# tick-box-1591b-mk-1_0.net
KiCad netlist of a schematic drawn in EAGLE
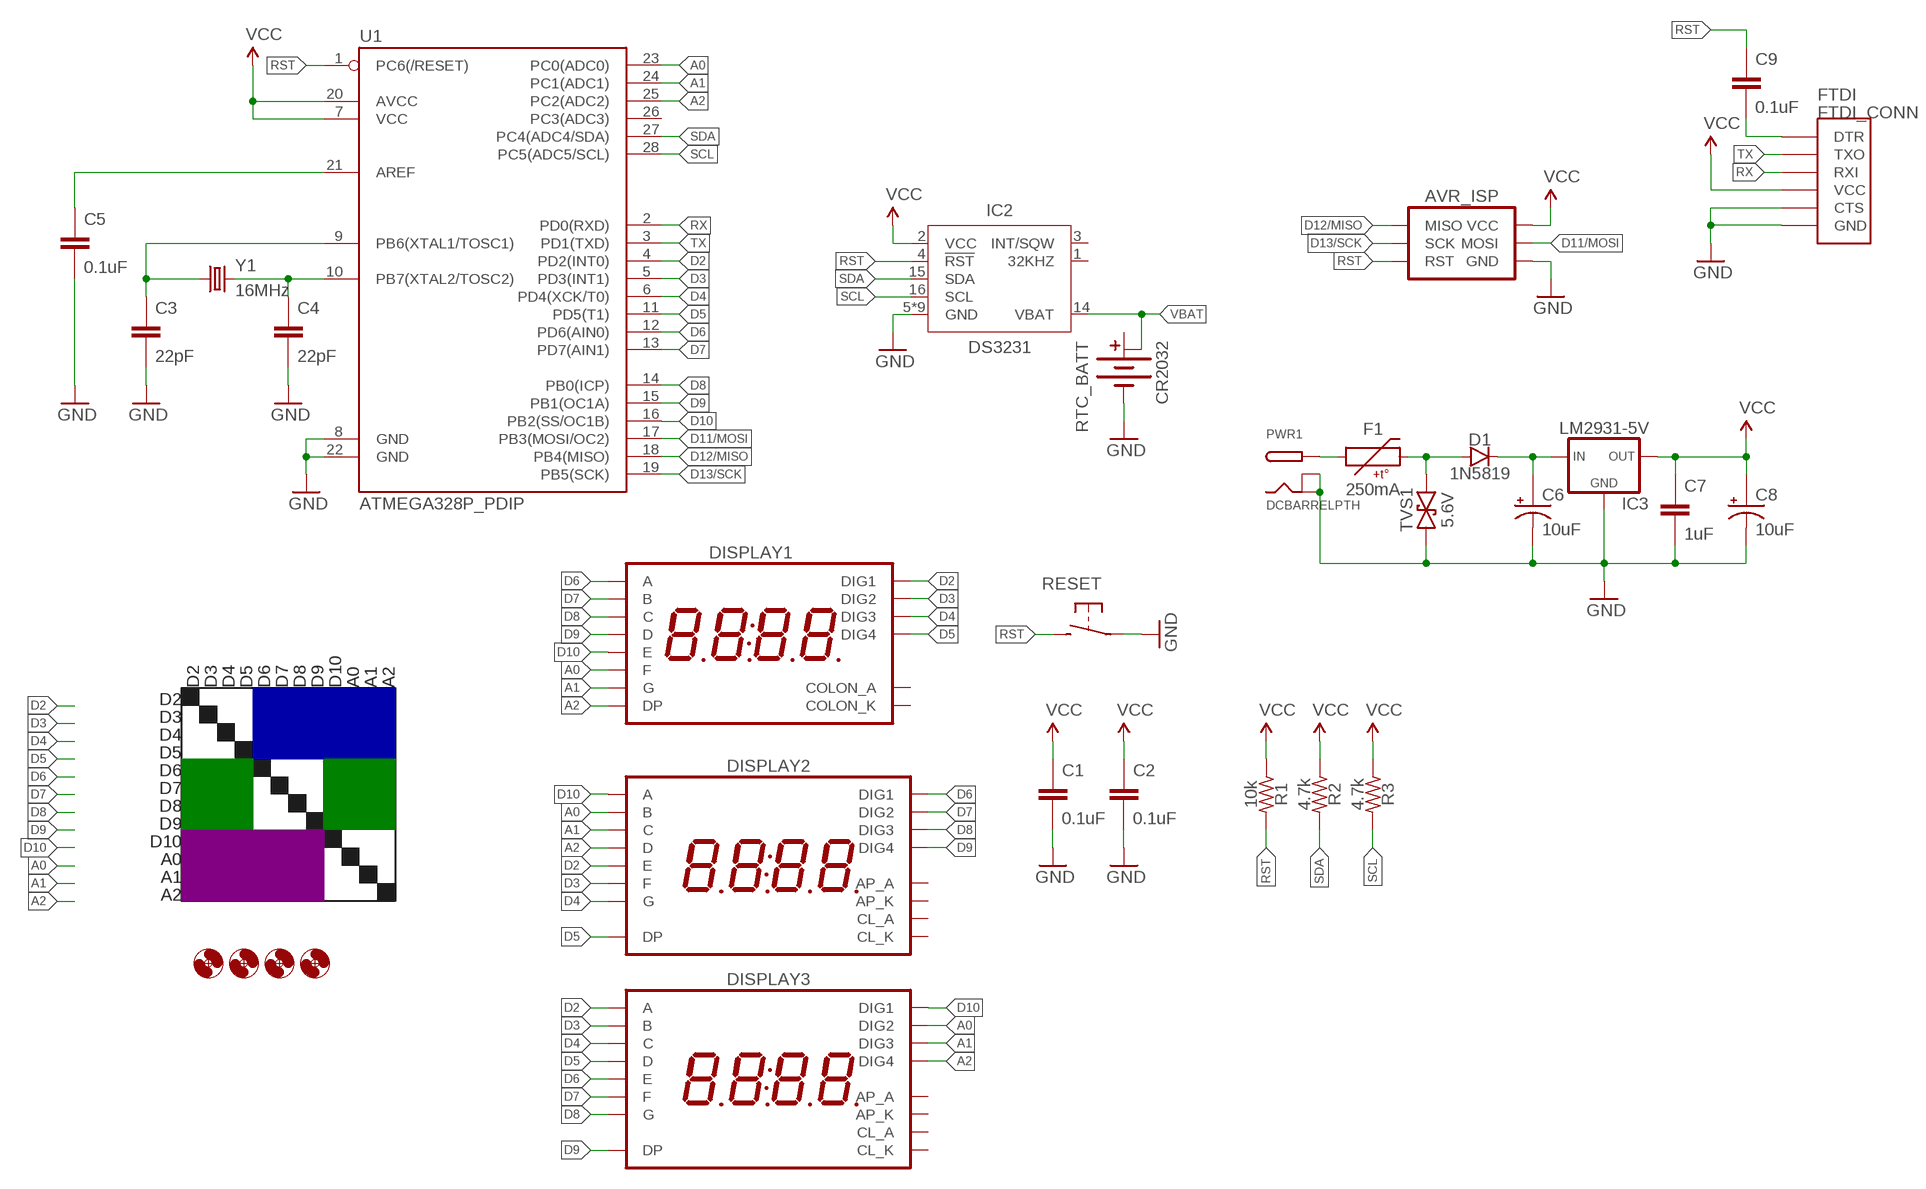
[diagram p0: schematic, sheet 1]

(export (version "E")
  (design (tool "Eeschema 10.0.6"))
  (components
    (comp (ref "AVR_ISP")
      (value "AVR_SPI_PRG_6PTH")
      (footprint "eagle-import:2X3")
      (libsource (lib "eagle-import") (part "AVR_SPI_PRG_6PTH"))
    )
    (comp (ref "C1")
      (value "0.1uF")
      (footprint "eagle-import:C025-024X044")
      (libsource (lib "eagle-import") (part "CAPACITOR-CERAMIC025-024X044"))
    )
    (comp (ref "C2")
      (value "0.1uF")
      (footprint "eagle-import:C025-024X044")
      (libsource (lib "eagle-import") (part "CAPACITOR-CERAMIC025-024X044"))
    )
    (comp (ref "C3")
      (value "22pF")
      (footprint "eagle-import:C025-024X044")
      (libsource (lib "eagle-import") (part "CAPACITOR-CERAMIC025-024X044"))
    )
    (comp (ref "C4")
      (value "22pF")
      (footprint "eagle-import:C025-024X044")
      (libsource (lib "eagle-import") (part "CAPACITOR-CERAMIC025-024X044"))
    )
    (comp (ref "C5")
      (value "0.1uF")
      (footprint "eagle-import:C025-024X044")
      (libsource (lib "eagle-import") (part "CAPACITOR-CERAMIC025-024X044"))
    )
    (comp (ref "C6")
      (value "10uF")
      (footprint "eagle-import:E2-5")
      (libsource (lib "eagle-import") (part "CAPACITOR-POLARIZEDE2-5"))
    )
    (comp (ref "C7")
      (value "1uF")
      (footprint "eagle-import:C025-024X044")
      (libsource (lib "eagle-import") (part "CAPACITOR-CERAMIC025-024X044"))
    )
    (comp (ref "C8")
      (value "10uF")
      (footprint "eagle-import:E2-5")
      (libsource (lib "eagle-import") (part "CAPACITOR-POLARIZEDE2-5"))
    )
    (comp (ref "C9")
      (value "0.1uF")
      (footprint "eagle-import:C025-024X044")
      (libsource (lib "eagle-import") (part "CAPACITOR-CERAMIC025-024X044"))
    )
    (comp (ref "D1")
      (value "1N5819")
      (footprint "eagle-import:DIODE-10.16MM")
      (libsource (lib "eagle-import") (part "DIODEPTH-10.68MM"))
    )
    (comp (ref "DISPLAY1")
      (value "7SEG_4DIGIT_COLON14.2MM-CC-NS")
      (footprint "eagle-import:7SEG_4DIG_NS")
      (libsource (lib "eagle-import") (part "7SEG_4DIGIT_COLON14.2MM-CC-NS"))
    )
    (comp (ref "DISPLAY2")
      (value "7SEG_4DIGIT_COLON_APOS")
      (footprint "eagle-import:7SEG_4DIG_10MM")
      (libsource (lib "eagle-import") (part "7SEG_4DIGIT_COLON_APOS"))
    )
    (comp (ref "DISPLAY3")
      (value "7SEG_4DIGIT_COLON_APOS")
      (footprint "eagle-import:7SEG_4DIG_10MM")
      (libsource (lib "eagle-import") (part "7SEG_4DIGIT_COLON_APOS"))
    )
    (comp (ref "F1")
      (value "250mA")
      (footprint "eagle-import:PTC-PTH-5.08MM")
      (libsource (lib "eagle-import") (part "PTCPTH-5.08MM"))
    )
    (comp (ref "FTDI")
      (value "FTDI_CONN")
      (footprint "eagle-import:FTDI_CONN")
      (libsource (lib "eagle-import") (part "FTDI_CONN"))
    )
    (comp (ref "H1")
      (value "HOLE#2")
      (footprint "eagle-import:HOLE-#2")
      (libsource (lib "eagle-import") (part "HOLE#2"))
    )
    (comp (ref "H2")
      (value "HOLE#2")
      (footprint "eagle-import:HOLE-#2")
      (libsource (lib "eagle-import") (part "HOLE#2"))
    )
    (comp (ref "H3")
      (value "HOLE#2")
      (footprint "eagle-import:HOLE-#2")
      (libsource (lib "eagle-import") (part "HOLE#2"))
    )
    (comp (ref "H4")
      (value "HOLE#2")
      (footprint "eagle-import:HOLE-#2")
      (libsource (lib "eagle-import") (part "HOLE#2"))
    )
    (comp (ref "IC2")
      (value "DS3231")
      (footprint "eagle-import:SO16W")
      (libsource (lib "eagle-import") (part "DS3231"))
    )
    (comp (ref "IC3")
      (value "LM2931-5V")
      (footprint "eagle-import:TO220-IGO-THERMPAD")
      (libsource (lib "eagle-import") (part "V_REG_78XXTO-220-THERMPAD"))
    )
    (comp (ref "PWR1")
      (value "DCBARRELPTH")
      (footprint "eagle-import:DCJACK_2MM_PTH")
      (libsource (lib "eagle-import") (part "DCBARRELPTH"))
    )
    (comp (ref "R1")
      (value "10k")
      (footprint "eagle-import:RESISTOR-AXIAL-PTH-7.62MM")
      (libsource (lib "eagle-import") (part "RESISTORPTH-AXIAL-7.62MM"))
    )
    (comp (ref "R2")
      (value "4.7k")
      (footprint "eagle-import:RESISTOR-AXIAL-PTH-7.62MM")
      (libsource (lib "eagle-import") (part "RESISTORPTH-AXIAL-7.62MM"))
    )
    (comp (ref "R3")
      (value "4.7k")
      (footprint "eagle-import:RESISTOR-AXIAL-PTH-7.62MM")
      (libsource (lib "eagle-import") (part "RESISTORPTH-AXIAL-7.62MM"))
    )
    (comp (ref "RESET")
      (value "SPST-NO-TACT6MM-PTH-SMALL-PADS")
      (footprint "eagle-import:DTS-6-SMALL-PADS")
      (libsource (lib "eagle-import") (part "SPST-NO-TACT6MM-PTH-SMALL-PADS"))
    )
    (comp (ref "RTC_BATT")
      (value "CR2032")
      (footprint "eagle-import:BATTCON_20MM_MINE")
      (libsource (lib "eagle-import") (part "BATTERY-COINCR2032_SMD"))
    )
    (comp (ref "TVS1")
      (value "5.6V")
      (footprint "eagle-import:DO-41-TVS")
      (libsource (lib "eagle-import") (part "TVSDO-41-TVS-BIDIRECTIONAL"))
    )
    (comp (ref "U1")
      (value "ATMEGA328P_PDIP")
      (footprint "eagle-import:DIL28-3")
      (libsource (lib "eagle-import") (part "ATMEGA328P_PDIP"))
    )
    (comp (ref "Y1")
      (value "16MHz")
      (footprint "eagle-import:HC49U-V")
      (libsource (lib "eagle-import") (part "CRYSTALHC49UV"))
    )
  )
  (nets
    (net (code "1") (name "A0") (class "Default")
      (node (ref "DISPLAY1") (pin "P$12") (pinfunction "F_P$12") (pintype "passive"))
      (node (ref "DISPLAY2") (pin "16") (pinfunction "B_16") (pintype "passive"))
      (node (ref "DISPLAY3") (pin "2") (pinfunction "DIG2_2") (pintype "passive"))
      (node (ref "U1") (pin "23") (pinfunction "PC0(ADC0)_23") (pintype "bidirectional"))
    )
    (net (code "2") (name "A1") (class "Default")
      (node (ref "DISPLAY1") (pin "P$5") (pinfunction "G_P$5") (pintype "passive"))
      (node (ref "DISPLAY2") (pin "13") (pinfunction "C_13") (pintype "passive"))
      (node (ref "DISPLAY3") (pin "6") (pinfunction "DIG3_6") (pintype "passive"))
      (node (ref "U1") (pin "24") (pinfunction "PC1(ADC1)_24") (pintype "bidirectional"))
    )
    (net (code "3") (name "A2") (class "Default")
      (node (ref "DISPLAY1") (pin "P$3") (pinfunction "DP_P$3") (pintype "passive"))
      (node (ref "DISPLAY2") (pin "3") (pinfunction "D_3") (pintype "passive"))
      (node (ref "DISPLAY3") (pin "8") (pinfunction "DIG4_8") (pintype "passive"))
      (node (ref "U1") (pin "25") (pinfunction "PC2(ADC2)_25") (pintype "bidirectional"))
    )
    (net (code "4") (name "D2") (class "Default")
      (node (ref "DISPLAY1") (pin "P$14") (pinfunction "DIG1_P$14") (pintype "passive"))
      (node (ref "DISPLAY2") (pin "5") (pinfunction "E_5") (pintype "passive"))
      (node (ref "DISPLAY3") (pin "14") (pinfunction "A_14") (pintype "passive"))
      (node (ref "U1") (pin "4") (pinfunction "PD2(INT0)_4") (pintype "bidirectional"))
    )
    (net (code "5") (name "D3") (class "Default")
      (node (ref "DISPLAY1") (pin "P$11") (pinfunction "DIG2_P$11") (pintype "passive"))
      (node (ref "DISPLAY2") (pin "11") (pinfunction "F_11") (pintype "passive"))
      (node (ref "DISPLAY3") (pin "16") (pinfunction "B_16") (pintype "passive"))
      (node (ref "U1") (pin "5") (pinfunction "PD3(INT1)_5") (pintype "bidirectional"))
    )
    (net (code "6") (name "D4") (class "Default")
      (node (ref "DISPLAY1") (pin "P$10") (pinfunction "DIG3_P$10") (pintype "passive"))
      (node (ref "DISPLAY2") (pin "15") (pinfunction "G_15") (pintype "passive"))
      (node (ref "DISPLAY3") (pin "13") (pinfunction "C_13") (pintype "passive"))
      (node (ref "U1") (pin "6") (pinfunction "PD4(XCK/T0)_6") (pintype "bidirectional"))
    )
    (net (code "7") (name "D5") (class "Default")
      (node (ref "DISPLAY1") (pin "P$6") (pinfunction "DIG4_P$6") (pintype "passive"))
      (node (ref "DISPLAY2") (pin "7") (pinfunction "DP_7") (pintype "passive"))
      (node (ref "DISPLAY3") (pin "3") (pinfunction "D_3") (pintype "passive"))
      (node (ref "U1") (pin "11") (pinfunction "PD5(T1)_11") (pintype "bidirectional"))
    )
    (net (code "8") (name "D6") (class "Default")
      (node (ref "DISPLAY1") (pin "P$13") (pinfunction "A_P$13") (pintype "passive"))
      (node (ref "DISPLAY2") (pin "1") (pinfunction "DIG1_1") (pintype "passive"))
      (node (ref "DISPLAY3") (pin "5") (pinfunction "E_5") (pintype "passive"))
      (node (ref "U1") (pin "12") (pinfunction "PD6(AIN0)_12") (pintype "bidirectional"))
    )
    (net (code "9") (name "D7") (class "Default")
      (node (ref "DISPLAY1") (pin "P$9") (pinfunction "B_P$9") (pintype "passive"))
      (node (ref "DISPLAY2") (pin "2") (pinfunction "DIG2_2") (pintype "passive"))
      (node (ref "DISPLAY3") (pin "11") (pinfunction "F_11") (pintype "passive"))
      (node (ref "U1") (pin "13") (pinfunction "PD7(AIN1)_13") (pintype "bidirectional"))
    )
    (net (code "10") (name "D8") (class "Default")
      (node (ref "DISPLAY1") (pin "P$4") (pinfunction "C_P$4") (pintype "passive"))
      (node (ref "DISPLAY2") (pin "6") (pinfunction "DIG3_6") (pintype "passive"))
      (node (ref "DISPLAY3") (pin "15") (pinfunction "G_15") (pintype "passive"))
      (node (ref "U1") (pin "14") (pinfunction "PB0(ICP)_14") (pintype "bidirectional"))
    )
    (net (code "11") (name "D9") (class "Default")
      (node (ref "DISPLAY1") (pin "P$2") (pinfunction "D_P$2") (pintype "passive"))
      (node (ref "DISPLAY2") (pin "8") (pinfunction "DIG4_8") (pintype "passive"))
      (node (ref "DISPLAY3") (pin "7") (pinfunction "DP_7") (pintype "passive"))
      (node (ref "U1") (pin "15") (pinfunction "PB1(OC1A)_15") (pintype "bidirectional"))
    )
    (net (code "12") (name "D10") (class "Default")
      (node (ref "DISPLAY1") (pin "P$1") (pinfunction "E_P$1") (pintype "passive"))
      (node (ref "DISPLAY2") (pin "14") (pinfunction "A_14") (pintype "passive"))
      (node (ref "DISPLAY3") (pin "1") (pinfunction "DIG1_1") (pintype "passive"))
      (node (ref "U1") (pin "16") (pinfunction "PB2(SS/OC1B)_16") (pintype "bidirectional"))
    )
    (net (code "13") (name "D11{slash}MOSI") (class "Default")
      (node (ref "AVR_ISP") (pin "4") (pinfunction "MOSI_4") (pintype "passive"))
      (node (ref "U1") (pin "17") (pinfunction "PB3(MOSI/OC2)_17") (pintype "bidirectional"))
    )
    (net (code "14") (name "D12{slash}MISO") (class "Default")
      (node (ref "AVR_ISP") (pin "1") (pinfunction "MISO_1") (pintype "passive"))
      (node (ref "U1") (pin "18") (pinfunction "PB4(MISO)_18") (pintype "bidirectional"))
    )
    (net (code "15") (name "D13{slash}SCK") (class "Default")
      (node (ref "AVR_ISP") (pin "3") (pinfunction "SCK_3") (pintype "passive"))
      (node (ref "U1") (pin "19") (pinfunction "PB5(SCK)_19") (pintype "bidirectional"))
    )
    (net (code "16") (name "GND") (class "Default")
      (node (ref "AVR_ISP") (pin "6") (pinfunction "GND_6") (pintype "passive"))
      (node (ref "C1") (pin "2") (pinfunction "2_2") (pintype "passive"))
      (node (ref "C2") (pin "2") (pinfunction "2_2") (pintype "passive"))
      (node (ref "C3") (pin "2") (pinfunction "2_2") (pintype "passive"))
      (node (ref "C4") (pin "2") (pinfunction "2_2") (pintype "passive"))
      (node (ref "C5") (pin "2") (pinfunction "2_2") (pintype "passive"))
      (node (ref "C6") (pin "-") (pinfunction "-_-") (pintype "passive"))
      (node (ref "C7") (pin "2") (pinfunction "2_2") (pintype "passive"))
      (node (ref "C8") (pin "-") (pinfunction "-_-") (pintype "passive"))
      (node (ref "FTDI") (pin "CTS") (pinfunction "CTS_CTS") (pintype "bidirectional"))
      (node (ref "FTDI") (pin "GND") (pinfunction "GND_GND") (pintype "bidirectional"))
      (node (ref "IC2") (pin "10") (pinfunction "GND_10") (pintype "bidirectional"))
      (node (ref "IC2") (pin "11") (pinfunction "GND_11") (pintype "bidirectional"))
      (node (ref "IC2") (pin "12") (pinfunction "GND_12") (pintype "bidirectional"))
      (node (ref "IC2") (pin "13") (pinfunction "GND_13") (pintype "bidirectional"))
      (node (ref "IC2") (pin "5") (pinfunction "GND_5") (pintype "bidirectional"))
      (node (ref "IC2") (pin "6") (pinfunction "GND_6") (pintype "bidirectional"))
      (node (ref "IC2") (pin "7") (pinfunction "GND_7") (pintype "bidirectional"))
      (node (ref "IC2") (pin "8") (pinfunction "GND_8") (pintype "bidirectional"))
      (node (ref "IC2") (pin "9") (pinfunction "GND_9") (pintype "bidirectional"))
      (node (ref "IC3") (pin "4") (pinfunction "GND_4") (pintype "bidirectional"))
      (node (ref "IC3") (pin "GND") (pinfunction "GND_GND") (pintype "bidirectional"))
      (node (ref "PWR1") (pin "BRK") (pinfunction "BRK_BRK") (pintype "bidirectional"))
      (node (ref "PWR1") (pin "GND") (pinfunction "GND_GND") (pintype "bidirectional"))
      (node (ref "RESET") (pin "1") (pinfunction "1_1") (pintype "passive"))
      (node (ref "RESET") (pin "2") (pinfunction "1_2") (pintype "passive"))
      (node (ref "RTC_BATT") (pin "BOTTOM") (pinfunction "-_BOTTOM") (pintype "bidirectional"))
      (node (ref "TVS1") (pin "P$1") (pinfunction "1_P$1") (pintype "passive"))
      (node (ref "U1") (pin "22") (pinfunction "GND_22") (pintype "bidirectional"))
      (node (ref "U1") (pin "8") (pinfunction "GND_8") (pintype "bidirectional"))
    )
    (net (code "17") (name "Net-(C6-Pad+)") (class "Default")
      (node (ref "C6") (pin "+") (pinfunction "+_+") (pintype "passive"))
      (node (ref "D1") (pin "C") (pinfunction "C_C") (pintype "passive"))
      (node (ref "IC3") (pin "IN") (pinfunction "IN_IN") (pintype "bidirectional"))
    )
    (net (code "18") (name "Net-(C9-Pad2)") (class "Default")
      (node (ref "C9") (pin "2") (pinfunction "2_2") (pintype "passive"))
      (node (ref "FTDI") (pin "DTR") (pinfunction "DTR_DTR") (pintype "bidirectional"))
    )
    (net (code "19") (name "Net-(F1-1)") (class "Default")
      (node (ref "F1") (pin "P$1") (pinfunction "1_P$1") (pintype "passive"))
      (node (ref "PWR1") (pin "PWR") (pinfunction "PWR_PWR") (pintype "bidirectional"))
    )
    (net (code "20") (name "Net-(F1-2)") (class "Default")
      (node (ref "D1") (pin "A") (pinfunction "A_A") (pintype "passive"))
      (node (ref "F1") (pin "P$2") (pinfunction "2_P$2") (pintype "passive"))
      (node (ref "TVS1") (pin "P$2") (pinfunction "2_P$2") (pintype "passive"))
    )
    (net (code "21") (name "Net-(U1-AREF)") (class "Default")
      (node (ref "C5") (pin "1") (pinfunction "1_1") (pintype "passive"))
      (node (ref "U1") (pin "21") (pinfunction "AREF_21") (pintype "bidirectional"))
    )
    (net (code "22") (name "Net-(U1-PB6(XTAL1{slash}TOSC1))") (class "Default")
      (node (ref "C3") (pin "1") (pinfunction "1_1") (pintype "passive"))
      (node (ref "U1") (pin "9") (pinfunction "PB6(XTAL1/TOSC1)_9") (pintype "bidirectional"))
      (node (ref "Y1") (pin "1") (pinfunction "1_1") (pintype "passive"))
    )
    (net (code "23") (name "Net-(U1-PB7(XTAL2{slash}TOSC2))") (class "Default")
      (node (ref "C4") (pin "1") (pinfunction "1_1") (pintype "passive"))
      (node (ref "U1") (pin "10") (pinfunction "PB7(XTAL2/TOSC2)_10") (pintype "bidirectional"))
      (node (ref "Y1") (pin "2") (pinfunction "2_2") (pintype "passive"))
    )
    (net (code "24") (name "RST") (class "Default")
      (node (ref "AVR_ISP") (pin "5") (pinfunction "RST_5") (pintype "passive"))
      (node (ref "C9") (pin "1") (pinfunction "1_1") (pintype "passive"))
      (node (ref "IC2") (pin "4") (pinfunction "~{RST}_4") (pintype "bidirectional"))
      (node (ref "R1") (pin "P$2") (pinfunction "2_P$2") (pintype "passive"))
      (node (ref "RESET") (pin "3") (pinfunction "2_3") (pintype "passive"))
      (node (ref "RESET") (pin "4") (pinfunction "2_4") (pintype "passive"))
      (node (ref "U1") (pin "1") (pinfunction "PC6(/RESET)_1") (pintype "bidirectional"))
    )
    (net (code "25") (name "RX") (class "Default")
      (node (ref "FTDI") (pin "RXI") (pinfunction "RXI_RXI") (pintype "bidirectional"))
      (node (ref "U1") (pin "2") (pinfunction "PD0(RXD)_2") (pintype "bidirectional"))
    )
    (net (code "26") (name "SCL") (class "Default")
      (node (ref "IC2") (pin "16") (pinfunction "SCL_16") (pintype "bidirectional"))
      (node (ref "R3") (pin "P$2") (pinfunction "2_P$2") (pintype "passive"))
      (node (ref "U1") (pin "28") (pinfunction "PC5(ADC5/SCL)_28") (pintype "bidirectional"))
    )
    (net (code "27") (name "SDA") (class "Default")
      (node (ref "IC2") (pin "15") (pinfunction "SDA_15") (pintype "bidirectional"))
      (node (ref "R2") (pin "P$2") (pinfunction "2_P$2") (pintype "passive"))
      (node (ref "U1") (pin "27") (pinfunction "PC4(ADC4/SDA)_27") (pintype "bidirectional"))
    )
    (net (code "28") (name "TX") (class "Default")
      (node (ref "FTDI") (pin "TXO") (pinfunction "TXO_TXO") (pintype "bidirectional"))
      (node (ref "U1") (pin "3") (pinfunction "PD1(TXD)_3") (pintype "bidirectional"))
    )
    (net (code "29") (name "VBAT") (class "Default")
      (node (ref "IC2") (pin "14") (pinfunction "VBAT_14") (pintype "bidirectional"))
      (node (ref "RTC_BATT") (pin "TOP@2") (pinfunction "+1_TOP@2") (pintype "bidirectional"))
    )
    (net (code "30") (name "VCC") (class "Default")
      (node (ref "AVR_ISP") (pin "2") (pinfunction "VCC_2") (pintype "passive"))
      (node (ref "C1") (pin "1") (pinfunction "1_1") (pintype "passive"))
      (node (ref "C2") (pin "1") (pinfunction "1_1") (pintype "passive"))
      (node (ref "C7") (pin "1") (pinfunction "1_1") (pintype "passive"))
      (node (ref "C8") (pin "+") (pinfunction "+_+") (pintype "passive"))
      (node (ref "FTDI") (pin "VCC") (pinfunction "VCC_VCC") (pintype "bidirectional"))
      (node (ref "IC2") (pin "2") (pinfunction "VCC_2") (pintype "bidirectional"))
      (node (ref "IC3") (pin "OUT") (pinfunction "OUT_OUT") (pintype "bidirectional"))
      (node (ref "R1") (pin "P$1") (pinfunction "1_P$1") (pintype "passive"))
      (node (ref "R2") (pin "P$1") (pinfunction "1_P$1") (pintype "passive"))
      (node (ref "R3") (pin "P$1") (pinfunction "1_P$1") (pintype "passive"))
      (node (ref "U1") (pin "20") (pinfunction "AVCC_20") (pintype "bidirectional"))
      (node (ref "U1") (pin "7") (pinfunction "VCC_7") (pintype "bidirectional"))
    )
    (net (code "31") (name "unconnected-(DISPLAY1-COLON_A-PadP$8)") (class "Default")
      (node (ref "DISPLAY1") (pin "P$8") (pinfunction "COLON_A_P$8") (pintype "passive"))
    )
    (net (code "32") (name "unconnected-(DISPLAY1-COLON_K-PadP$7)") (class "Default")
      (node (ref "DISPLAY1") (pin "P$7") (pinfunction "COLON_K_P$7") (pintype "passive"))
    )
    (net (code "33") (name "unconnected-(DISPLAY2-AP_A-Pad10)") (class "Default")
      (node (ref "DISPLAY2") (pin "10") (pinfunction "AP_A_10") (pintype "bidirectional"))
    )
    (net (code "34") (name "unconnected-(DISPLAY2-AP_K-Pad9)") (class "Default")
      (node (ref "DISPLAY2") (pin "9") (pinfunction "AP_K_9") (pintype "bidirectional"))
    )
    (net (code "35") (name "unconnected-(DISPLAY2-CL_A-Pad4)") (class "Default")
      (node (ref "DISPLAY2") (pin "4") (pinfunction "CL_A_4") (pintype "passive"))
    )
    (net (code "36") (name "unconnected-(DISPLAY2-CL_K-Pad12)") (class "Default")
      (node (ref "DISPLAY2") (pin "12") (pinfunction "CL_K_12") (pintype "passive"))
    )
    (net (code "37") (name "unconnected-(DISPLAY3-AP_A-Pad10)") (class "Default")
      (node (ref "DISPLAY3") (pin "10") (pinfunction "AP_A_10") (pintype "bidirectional"))
    )
    (net (code "38") (name "unconnected-(DISPLAY3-AP_K-Pad9)") (class "Default")
      (node (ref "DISPLAY3") (pin "9") (pinfunction "AP_K_9") (pintype "bidirectional"))
    )
    (net (code "39") (name "unconnected-(DISPLAY3-CL_A-Pad4)") (class "Default")
      (node (ref "DISPLAY3") (pin "4") (pinfunction "CL_A_4") (pintype "passive"))
    )
    (net (code "40") (name "unconnected-(DISPLAY3-CL_K-Pad12)") (class "Default")
      (node (ref "DISPLAY3") (pin "12") (pinfunction "CL_K_12") (pintype "passive"))
    )
    (net (code "41") (name "unconnected-(IC2-32KHZ-Pad1)") (class "Default")
      (node (ref "IC2") (pin "1") (pinfunction "32KHZ_1") (pintype "bidirectional"))
    )
    (net (code "42") (name "unconnected-(IC2-INT{slash}SQW-Pad3)") (class "Default")
      (node (ref "IC2") (pin "3") (pinfunction "INT/SQW_3") (pintype "bidirectional"))
    )
    (net (code "43") (name "unconnected-(RTC_BATT-+-PadTOP@1)") (class "Default")
      (node (ref "RTC_BATT") (pin "TOP@1") (pinfunction "+_TOP@1") (pintype "bidirectional"))
    )
    (net (code "44") (name "unconnected-(U1-PC3(ADC3)-Pad26)") (class "Default")
      (node (ref "U1") (pin "26") (pinfunction "PC3(ADC3)_26") (pintype "bidirectional"))
    )
  )
)
